# FPGA.net
KiCad netlist of a schematic drawn in Altium Designer
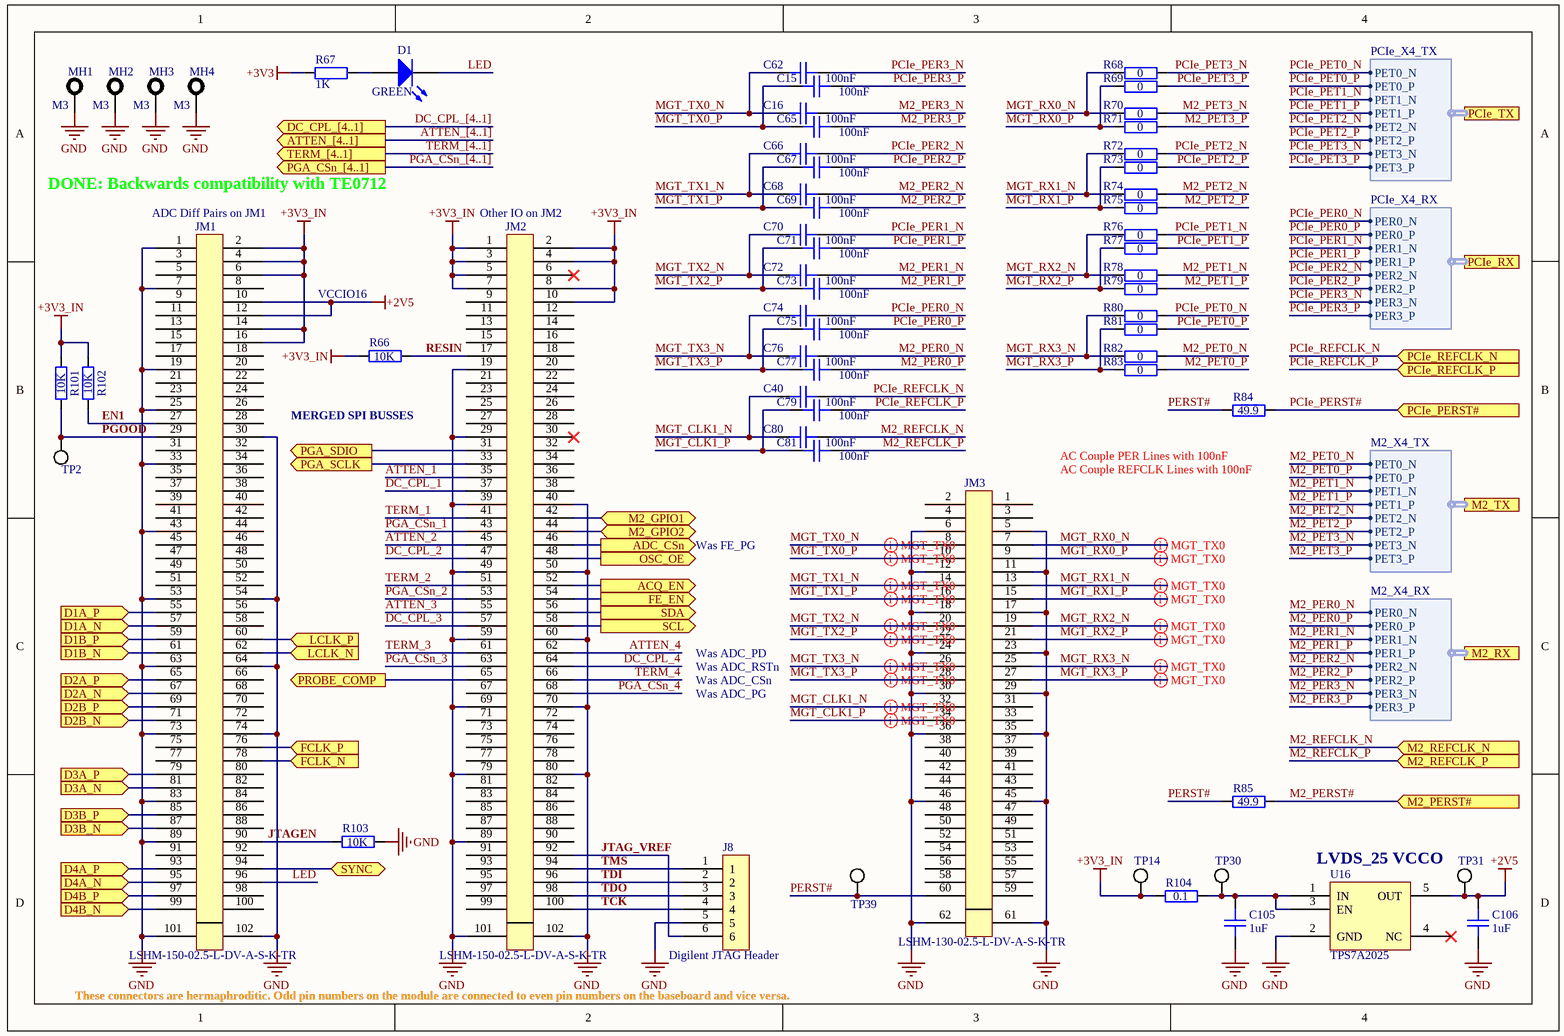
[diagram p0: FPGA.SchDoc]

(export (version "E")
  (design (tool "Eeschema 10.0.6"))
  (components
    (comp (ref "C15")
      (value "100nF")
      (footprint "GEN_C_0201")
      (libsource (lib "DSO") (part "CAP 100nF 6.3V X5R 0201"))
    )
    (comp (ref "C16")
      (value "100nF")
      (footprint "GEN_C_0201")
      (libsource (lib "DSO") (part "CAP 100nF 6.3V X5R 0201"))
    )
    (comp (ref "C40")
      (value "100nF")
      (footprint "GEN_C_0201")
      (libsource (lib "DSO") (part "CAP 100nF 6.3V X5R 0201"))
    )
    (comp (ref "C62")
      (value "100nF")
      (footprint "GEN_C_0201")
      (libsource (lib "DSO") (part "CAP 100nF 6.3V X5R 0201"))
    )
    (comp (ref "C65")
      (value "100nF")
      (footprint "GEN_C_0201")
      (libsource (lib "DSO") (part "CAP 100nF 6.3V X5R 0201"))
    )
    (comp (ref "C66")
      (value "100nF")
      (footprint "GEN_C_0201")
      (libsource (lib "DSO") (part "CAP 100nF 6.3V X5R 0201"))
    )
    (comp (ref "C67")
      (value "100nF")
      (footprint "GEN_C_0201")
      (libsource (lib "DSO") (part "CAP 100nF 6.3V X5R 0201"))
    )
    (comp (ref "C68")
      (value "100nF")
      (footprint "GEN_C_0201")
      (libsource (lib "DSO") (part "CAP 100nF 6.3V X5R 0201"))
    )
    (comp (ref "C69")
      (value "100nF")
      (footprint "GEN_C_0201")
      (libsource (lib "DSO") (part "CAP 100nF 6.3V X5R 0201"))
    )
    (comp (ref "C70")
      (value "100nF")
      (footprint "GEN_C_0201")
      (libsource (lib "DSO") (part "CAP 100nF 6.3V X5R 0201"))
    )
    (comp (ref "C71")
      (value "100nF")
      (footprint "GEN_C_0201")
      (libsource (lib "DSO") (part "CAP 100nF 6.3V X5R 0201"))
    )
    (comp (ref "C72")
      (value "100nF")
      (footprint "GEN_C_0201")
      (libsource (lib "DSO") (part "CAP 100nF 6.3V X5R 0201"))
    )
    (comp (ref "C73")
      (value "100nF")
      (footprint "GEN_C_0201")
      (libsource (lib "DSO") (part "CAP 100nF 6.3V X5R 0201"))
    )
    (comp (ref "C74")
      (value "100nF")
      (footprint "GEN_C_0201")
      (libsource (lib "DSO") (part "CAP 100nF 6.3V X5R 0201"))
    )
    (comp (ref "C75")
      (value "100nF")
      (footprint "GEN_C_0201")
      (libsource (lib "DSO") (part "CAP 100nF 6.3V X5R 0201"))
    )
    (comp (ref "C76")
      (value "100nF")
      (footprint "GEN_C_0201")
      (libsource (lib "DSO") (part "CAP 100nF 6.3V X5R 0201"))
    )
    (comp (ref "C77")
      (value "100nF")
      (footprint "GEN_C_0201")
      (libsource (lib "DSO") (part "CAP 100nF 6.3V X5R 0201"))
    )
    (comp (ref "C79")
      (value "100nF")
      (footprint "GEN_C_0201")
      (libsource (lib "DSO") (part "CAP 100nF 6.3V X5R 0201"))
    )
    (comp (ref "C80")
      (value "100nF")
      (footprint "GEN_C_0201")
      (libsource (lib "DSO") (part "CAP 100nF 6.3V X5R 0201"))
    )
    (comp (ref "C81")
      (value "100nF")
      (footprint "GEN_C_0201")
      (libsource (lib "DSO") (part "CAP 100nF 6.3V X5R 0201"))
    )
    (comp (ref "C105")
      (value "1uF")
      (footprint "GEN_C_0402")
      (libsource (lib "DSO") (part "CAP 1uF 25V X5R 0402"))
    )
    (comp (ref "C106")
      (value "1uF")
      (footprint "GEN_C_0402")
      (libsource (lib "DSO") (part "CAP 1uF 25V X5R 0402"))
    )
    (comp (ref "D1")
      (value "GREEN")
      (footprint "LED_0603_LTST-S270K")
      (libsource (lib "DSO") (part "LED GREEN 0603 LTST-S270K"))
    )
    (comp (ref "J8")
      (value "2.54mm 6 Pin TH")
      (footprint "GEN_2.54mm_6_Pin_TH_RA")
      (libsource (lib "DSO") (part "CONN 2.54mm 6 Pin TH RA"))
    )
    (comp (ref "JM1")
      (value "LSHM-150-02.5-L-DV-A-S-K-TR")
      (footprint "SAM_LSHM-150-XX.X-XX-DV-A-S")
      (fields (field (name "MANUFACTURER") "Samtec"))
      (libsource (lib "DSO") (part "CONN LSHM-150-02.5-L-DV-A-S-K-TR"))
    )
    (comp (ref "JM2")
      (value "LSHM-150-02.5-L-DV-A-S-K-TR")
      (footprint "SAM_LSHM-150-XX.X-XX-DV-A-S")
      (fields (field (name "MANUFACTURER") "Samtec"))
      (libsource (lib "DSO") (part "CONN LSHM-150-02.5-L-DV-A-S-K-TR"))
    )
    (comp (ref "JM3")
      (value "LSHM-130-02.5-L-DV-A-S-K-TR")
      (footprint "SAM_LSHM-130-XX.X-XX-DV-A-S")
      (fields (field (name "MANUFACTURER") "Samtec"))
      (libsource (lib "DSO") (part "CONN LSHM-130-02.5-L-DV-A-S-K-TR"))
    )
    (comp (ref "MH1") (value "M3") (footprint "MH M3") (libsource (lib "DSO") (part "MH M3")))
    (comp (ref "MH2") (value "M3") (footprint "MH M3") (libsource (lib "DSO") (part "MH M3")))
    (comp (ref "MH3") (value "M3") (footprint "MH M3") (libsource (lib "DSO") (part "MH M3")))
    (comp (ref "MH4") (value "M3") (footprint "MH M3") (libsource (lib "DSO") (part "MH M3")))
    (comp (ref "R66")
      (value "10K")
      (footprint "GEN_R_0402")
      (fields (field (name "TOLERANCE") "1%"))
      (libsource (lib "DSO") (part "RES 10K OHM 1% 1/10W 0402"))
    )
    (comp (ref "R67")
      (value "1K")
      (footprint "GEN_R_0402")
      (fields (field (name "TOLERANCE") "1%"))
      (libsource (lib "DSO") (part "RES 1K OHM 1% 1/10W 0402"))
    )
    (comp (ref "R68")
      (value "0")
      (footprint "GEN_R_0201")
      (fields (field (name "TOLERANCE") "1%"))
      (libsource (lib "DSO") (part "RES 0 OHM 1% 1/20W 0201"))
    )
    (comp (ref "R69")
      (value "0")
      (footprint "GEN_R_0201")
      (fields (field (name "TOLERANCE") "1%"))
      (libsource (lib "DSO") (part "RES 0 OHM 1% 1/20W 0201"))
    )
    (comp (ref "R70")
      (value "0")
      (footprint "GEN_R_0201")
      (fields (field (name "TOLERANCE") "1%"))
      (libsource (lib "DSO") (part "RES 0 OHM 1% 1/20W 0201"))
    )
    (comp (ref "R71")
      (value "0")
      (footprint "GEN_R_0201")
      (fields (field (name "TOLERANCE") "1%"))
      (libsource (lib "DSO") (part "RES 0 OHM 1% 1/20W 0201"))
    )
    (comp (ref "R72")
      (value "0")
      (footprint "GEN_R_0201")
      (fields (field (name "TOLERANCE") "1%"))
      (libsource (lib "DSO") (part "RES 0 OHM 1% 1/20W 0201"))
    )
    (comp (ref "R73")
      (value "0")
      (footprint "GEN_R_0201")
      (fields (field (name "TOLERANCE") "1%"))
      (libsource (lib "DSO") (part "RES 0 OHM 1% 1/20W 0201"))
    )
    (comp (ref "R74")
      (value "0")
      (footprint "GEN_R_0201")
      (fields (field (name "TOLERANCE") "1%"))
      (libsource (lib "DSO") (part "RES 0 OHM 1% 1/20W 0201"))
    )
    (comp (ref "R75")
      (value "0")
      (footprint "GEN_R_0201")
      (fields (field (name "TOLERANCE") "1%"))
      (libsource (lib "DSO") (part "RES 0 OHM 1% 1/20W 0201"))
    )
    (comp (ref "R76")
      (value "0")
      (footprint "GEN_R_0201")
      (fields (field (name "TOLERANCE") "1%"))
      (libsource (lib "DSO") (part "RES 0 OHM 1% 1/20W 0201"))
    )
    (comp (ref "R77")
      (value "0")
      (footprint "GEN_R_0201")
      (fields (field (name "TOLERANCE") "1%"))
      (libsource (lib "DSO") (part "RES 0 OHM 1% 1/20W 0201"))
    )
    (comp (ref "R78")
      (value "0")
      (footprint "GEN_R_0201")
      (fields (field (name "TOLERANCE") "1%"))
      (libsource (lib "DSO") (part "RES 0 OHM 1% 1/20W 0201"))
    )
    (comp (ref "R79")
      (value "0")
      (footprint "GEN_R_0201")
      (fields (field (name "TOLERANCE") "1%"))
      (libsource (lib "DSO") (part "RES 0 OHM 1% 1/20W 0201"))
    )
    (comp (ref "R80")
      (value "0")
      (footprint "GEN_R_0201")
      (fields (field (name "TOLERANCE") "1%"))
      (libsource (lib "DSO") (part "RES 0 OHM 1% 1/20W 0201"))
    )
    (comp (ref "R81")
      (value "0")
      (footprint "GEN_R_0201")
      (fields (field (name "TOLERANCE") "1%"))
      (libsource (lib "DSO") (part "RES 0 OHM 1% 1/20W 0201"))
    )
    (comp (ref "R82")
      (value "0")
      (footprint "GEN_R_0201")
      (fields (field (name "TOLERANCE") "1%"))
      (libsource (lib "DSO") (part "RES 0 OHM 1% 1/20W 0201"))
    )
    (comp (ref "R83")
      (value "0")
      (footprint "GEN_R_0201")
      (fields (field (name "TOLERANCE") "1%"))
      (libsource (lib "DSO") (part "RES 0 OHM 1% 1/20W 0201"))
    )
    (comp (ref "R84")
      (value "49.9")
      (footprint "GEN_R_0402")
      (fields (field (name "TOLERANCE") "1%"))
      (libsource (lib "DSO") (part "RES 49.9 OHM 1% 1/10W 0402"))
    )
    (comp (ref "R85")
      (value "49.9")
      (footprint "GEN_R_0402")
      (fields (field (name "TOLERANCE") "1%"))
      (libsource (lib "DSO") (part "RES 49.9 OHM 1% 1/10W 0402"))
    )
    (comp (ref "R101")
      (value "10K")
      (footprint "GEN_R_0402")
      (fields (field (name "TOLERANCE") "1%"))
      (libsource (lib "") (part "RES 10K OHM 1% 1/10W 0402_1"))
    )
    (comp (ref "R102")
      (value "10K")
      (footprint "GEN_R_0402")
      (fields (field (name "TOLERANCE") "1%"))
      (libsource (lib "") (part "RES 10K OHM 1% 1/10W 0402_1"))
    )
    (comp (ref "R103")
      (value "10K")
      (footprint "GEN_R_0402")
      (fields (field (name "TOLERANCE") "1%"))
      (libsource (lib "DSO") (part "RES 10K OHM 1% 1/10W 0402"))
    )
    (comp (ref "R104")
      (value "0.1")
      (footprint "GEN_R_0402")
      (fields (field (name "TOLERANCE") "1%"))
      (libsource (lib "DSO") (part "RES 0.1 OHM 1% 1/6W 0402"))
    )
    (comp (ref "TP2") (value "PCB") (footprint "GEN_TP_PCB") (libsource (lib "DSO") (part "TP PCB 1mm")))
    (comp (ref "TP14") (value "PCB") (footprint "GEN_TP_PCB") (libsource (lib "DSO") (part "TP PCB 1mm")))
    (comp (ref "TP30") (value "PCB") (footprint "GEN_TP_PCB") (libsource (lib "DSO") (part "TP PCB 1mm")))
    (comp (ref "TP31") (value "PCB") (footprint "GEN_TP_PCB") (libsource (lib "DSO") (part "TP PCB 1mm")))
    (comp (ref "TP39") (value "PCB") (footprint "GEN_TP_PCB") (libsource (lib "DSO") (part "TP PCB 1mm")))
    (comp (ref "U16")
      (value "TPS7A2025")
      (footprint "GEN_SOT23_5_950_2900X1600X1450")
      (libsource (lib "DSO") (part "IC LDO TPS7A2025"))
    )
  )
  (nets
    (net (code "5") (name "+2V5") (class "Default")
      (node (ref "C106") (pin "2") (pinfunction "2_2") (pintype "passive"))
      (node (ref "JM1") (pin "10") (pinfunction "10_10") (pintype "passive"))
      (node (ref "JM1") (pin "12") (pinfunction "12_12") (pintype "passive"))
      (node (ref "TP31") (pin "1") (pinfunction "1_1") (pintype "passive"))
      (node (ref "U16") (pin "5") (pinfunction "OUT_5") (pintype "power_in"))
    )
    (net (code "6") (name "+3V3") (class "Default")
      (node (ref "R67") (pin "2") (pinfunction "2_2") (pintype "passive"))
    )
    (net (code "7") (name "+3V3_IN") (class "Default")
      (node (ref "JM1") (pin "14") (pinfunction "14_14") (pintype "passive"))
      (node (ref "JM1") (pin "16") (pinfunction "16_16") (pintype "passive"))
      (node (ref "JM1") (pin "2") (pinfunction "2_2") (pintype "passive"))
      (node (ref "JM1") (pin "4") (pinfunction "4_4") (pintype "passive"))
      (node (ref "JM1") (pin "6") (pinfunction "6_6") (pintype "passive"))
      (node (ref "JM2") (pin "1") (pinfunction "1_1") (pintype "passive"))
      (node (ref "JM2") (pin "10") (pinfunction "10_10") (pintype "passive"))
      (node (ref "JM2") (pin "2") (pinfunction "2_2") (pintype "passive"))
      (node (ref "JM2") (pin "3") (pinfunction "3_3") (pintype "passive"))
      (node (ref "JM2") (pin "4") (pinfunction "4_4") (pintype "passive"))
      (node (ref "JM2") (pin "5") (pinfunction "5_5") (pintype "passive"))
      (node (ref "JM2") (pin "7") (pinfunction "7_7") (pintype "passive"))
      (node (ref "JM2") (pin "8") (pinfunction "8_8") (pintype "passive"))
      (node (ref "R101") (pin "2") (pinfunction "2_2") (pintype "passive"))
      (node (ref "R102") (pin "2") (pinfunction "2_2") (pintype "passive"))
      (node (ref "R104") (pin "1") (pinfunction "1_1") (pintype "passive"))
      (node (ref "R66") (pin "2") (pinfunction "2_2") (pintype "passive"))
      (node (ref "TP14") (pin "1") (pinfunction "1_1") (pintype "passive"))
    )
    (net (code "8") (name "/ACQ_EN") (class "Default")
      (node (ref "JM2") (pin "52") (pinfunction "52_52") (pintype "passive"))
    )
    (net (code "9") (name "/ADC_CSn") (class "Default")
      (node (ref "JM2") (pin "46") (pinfunction "46_46") (pintype "passive"))
    )
    (net (code "10") (name "/ATTEN_1") (class "Default")
      (node (ref "JM2") (pin "35") (pinfunction "35_35") (pintype "passive"))
    )
    (net (code "11") (name "/ATTEN_2") (class "Default")
      (node (ref "JM2") (pin "45") (pinfunction "45_45") (pintype "passive"))
    )
    (net (code "12") (name "/ATTEN_3") (class "Default")
      (node (ref "JM2") (pin "55") (pinfunction "55_55") (pintype "passive"))
    )
    (net (code "13") (name "/ATTEN_4") (class "Default")
      (node (ref "JM2") (pin "62") (pinfunction "62_62") (pintype "passive"))
    )
    (net (code "15") (name "/D1A_N") (class "Default")
      (node (ref "JM1") (pin "57") (pinfunction "57_57") (pintype "passive"))
    )
    (net (code "16") (name "/D1A_P") (class "Default")
      (node (ref "JM1") (pin "55") (pinfunction "55_55") (pintype "passive"))
    )
    (net (code "17") (name "/D1B_N") (class "Default")
      (node (ref "JM1") (pin "61") (pinfunction "61_61") (pintype "passive"))
    )
    (net (code "18") (name "/D1B_P") (class "Default")
      (node (ref "JM1") (pin "59") (pinfunction "59_59") (pintype "passive"))
    )
    (net (code "19") (name "/D2A_N") (class "Default")
      (node (ref "JM1") (pin "67") (pinfunction "67_67") (pintype "passive"))
    )
    (net (code "20") (name "/D2A_P") (class "Default")
      (node (ref "JM1") (pin "65") (pinfunction "65_65") (pintype "passive"))
    )
    (net (code "21") (name "/D2B_N") (class "Default")
      (node (ref "JM1") (pin "71") (pinfunction "71_71") (pintype "passive"))
    )
    (net (code "22") (name "/D2B_P") (class "Default")
      (node (ref "JM1") (pin "69") (pinfunction "69_69") (pintype "passive"))
    )
    (net (code "23") (name "/D3A_N") (class "Default")
      (node (ref "JM1") (pin "81") (pinfunction "81_81") (pintype "passive"))
    )
    (net (code "24") (name "/D3A_P") (class "Default")
      (node (ref "JM1") (pin "79") (pinfunction "79_79") (pintype "passive"))
    )
    (net (code "25") (name "/D3B_N") (class "Default")
      (node (ref "JM1") (pin "87") (pinfunction "87_87") (pintype "passive"))
    )
    (net (code "26") (name "/D3B_P") (class "Default")
      (node (ref "JM1") (pin "85") (pinfunction "85_85") (pintype "passive"))
    )
    (net (code "27") (name "/D4A_N") (class "Default")
      (node (ref "JM1") (pin "95") (pinfunction "95_95") (pintype "passive"))
    )
    (net (code "28") (name "/D4A_P") (class "Default")
      (node (ref "JM1") (pin "93") (pinfunction "93_93") (pintype "passive"))
    )
    (net (code "29") (name "/D4B_N") (class "Default")
      (node (ref "JM1") (pin "99") (pinfunction "99_99") (pintype "passive"))
    )
    (net (code "30") (name "/D4B_P") (class "Default")
      (node (ref "JM1") (pin "97") (pinfunction "97_97") (pintype "passive"))
    )
    (net (code "31") (name "/DC_CPL_1") (class "Default")
      (node (ref "JM2") (pin "37") (pinfunction "37_37") (pintype "passive"))
    )
    (net (code "32") (name "/DC_CPL_2") (class "Default")
      (node (ref "JM2") (pin "47") (pinfunction "47_47") (pintype "passive"))
    )
    (net (code "33") (name "/DC_CPL_3") (class "Default")
      (node (ref "JM2") (pin "57") (pinfunction "57_57") (pintype "passive"))
    )
    (net (code "34") (name "/DC_CPL_4") (class "Default")
      (node (ref "JM2") (pin "64") (pinfunction "64_64") (pintype "passive"))
    )
    (net (code "36") (name "/EN1") (class "Default")
      (node (ref "JM1") (pin "27") (pinfunction "27_27") (pintype "passive"))
      (node (ref "R102") (pin "1") (pinfunction "1_1") (pintype "passive"))
    )
    (net (code "37") (name "/FCLK_N") (class "Default")
      (node (ref "JM1") (pin "78") (pinfunction "78_78") (pintype "passive"))
    )
    (net (code "38") (name "/FCLK_P") (class "Default")
      (node (ref "JM1") (pin "76") (pinfunction "76_76") (pintype "passive"))
    )
    (net (code "39") (name "/FE_EN") (class "Default")
      (node (ref "JM2") (pin "54") (pinfunction "54_54") (pintype "passive"))
    )
    (net (code "40") (name "/JTAGEN") (class "Default")
      (node (ref "JM1") (pin "90") (pinfunction "90_90") (pintype "passive"))
      (node (ref "R103") (pin "2") (pinfunction "2_2") (pintype "passive"))
    )
    (net (code "41") (name "/JTAG_VREF") (class "Default")
      (node (ref "J8") (pin "6") (pinfunction "6_6") (pintype "passive"))
      (node (ref "JM2") (pin "92") (pinfunction "92_92") (pintype "passive"))
    )
    (net (code "42") (name "/LCLK_N") (class "Default")
      (node (ref "JM1") (pin "62") (pinfunction "62_62") (pintype "passive"))
    )
    (net (code "43") (name "/LCLK_P") (class "Default")
      (node (ref "JM1") (pin "60") (pinfunction "60_60") (pintype "passive"))
    )
    (net (code "44") (name "/LED") (class "Default")
      (node (ref "D1") (pin "1") (pinfunction "K_1") (pintype "passive"))
      (node (ref "JM1") (pin "96") (pinfunction "96_96") (pintype "passive"))
    )
    (net (code "45") (name "/M2_GPIO1") (class "Default")
      (node (ref "JM2") (pin "42") (pinfunction "42_42") (pintype "passive"))
    )
    (net (code "46") (name "/M2_GPIO2") (class "Default")
      (node (ref "JM2") (pin "44") (pinfunction "44_44") (pintype "passive"))
    )
    (net (code "47") (name "/M2_PER0_N") (class "Default")
      (node (ref "C76") (pin "1") (pinfunction "1_1") (pintype "passive"))
    )
    (net (code "48") (name "/M2_PER0_P") (class "Default")
      (node (ref "C77") (pin "1") (pinfunction "1_1") (pintype "passive"))
    )
    (net (code "49") (name "/M2_PER1_N") (class "Default")
      (node (ref "C72") (pin "1") (pinfunction "1_1") (pintype "passive"))
    )
    (net (code "50") (name "/M2_PER1_P") (class "Default")
      (node (ref "C73") (pin "1") (pinfunction "1_1") (pintype "passive"))
    )
    (net (code "51") (name "/M2_PER2_N") (class "Default")
      (node (ref "C68") (pin "1") (pinfunction "1_1") (pintype "passive"))
    )
    (net (code "52") (name "/M2_PER2_P") (class "Default")
      (node (ref "C69") (pin "1") (pinfunction "1_1") (pintype "passive"))
    )
    (net (code "53") (name "/M2_PER3_N") (class "Default")
      (node (ref "C16") (pin "1") (pinfunction "1_1") (pintype "passive"))
    )
    (net (code "54") (name "/M2_PER3_P") (class "Default")
      (node (ref "C65") (pin "1") (pinfunction "1_1") (pintype "passive"))
    )
    (net (code "55") (name "/M2_PERST#") (class "Default")
      (node (ref "R85") (pin "2") (pinfunction "2_2") (pintype "passive"))
    )
    (net (code "56") (name "/M2_PET0_N") (class "Default")
      (node (ref "R82") (pin "2") (pinfunction "2_2") (pintype "passive"))
    )
    (net (code "57") (name "/M2_PET0_P") (class "Default")
      (node (ref "R83") (pin "2") (pinfunction "2_2") (pintype "passive"))
    )
    (net (code "58") (name "/M2_PET1_N") (class "Default")
      (node (ref "R78") (pin "2") (pinfunction "2_2") (pintype "passive"))
    )
    (net (code "59") (name "/M2_PET1_P") (class "Default")
      (node (ref "R79") (pin "2") (pinfunction "2_2") (pintype "passive"))
    )
    (net (code "60") (name "/M2_PET2_N") (class "Default")
      (node (ref "R74") (pin "2") (pinfunction "2_2") (pintype "passive"))
    )
    (net (code "61") (name "/M2_PET2_P") (class "Default")
      (node (ref "R75") (pin "2") (pinfunction "2_2") (pintype "passive"))
    )
    (net (code "62") (name "/M2_PET3_N") (class "Default")
      (node (ref "R70") (pin "2") (pinfunction "2_2") (pintype "passive"))
    )
    (net (code "63") (name "/M2_PET3_P") (class "Default")
      (node (ref "R71") (pin "2") (pinfunction "2_2") (pintype "passive"))
    )
    (net (code "64") (name "/M2_REFCLK_N") (class "Default")
      (node (ref "C80") (pin "1") (pinfunction "1_1") (pintype "passive"))
    )
    (net (code "65") (name "/M2_REFCLK_P") (class "Default")
      (node (ref "C81") (pin "1") (pinfunction "1_1") (pintype "passive"))
    )
    (net (code "66") (name "/MGT_CLK1_N") (class "Default")
      (node (ref "C40") (pin "2") (pinfunction "2_2") (pintype "passive"))
      (node (ref "C80") (pin "2") (pinfunction "2_2") (pintype "passive"))
      (node (ref "JM3") (pin "32") (pinfunction "32_32") (pintype "passive"))
    )
    (net (code "67") (name "/MGT_CLK1_P") (class "Default")
      (node (ref "C79") (pin "2") (pinfunction "2_2") (pintype "passive"))
      (node (ref "C81") (pin "2") (pinfunction "2_2") (pintype "passive"))
      (node (ref "JM3") (pin "34") (pinfunction "34_34") (pintype "passive"))
    )
    (net (code "68") (name "/MGT_RX0_N") (class "Default")
      (node (ref "JM3") (pin "7") (pinfunction "7_7") (pintype "passive"))
      (node (ref "R68") (pin "1") (pinfunction "1_1") (pintype "passive"))
      (node (ref "R70") (pin "1") (pinfunction "1_1") (pintype "passive"))
    )
    (net (code "69") (name "/MGT_RX0_P") (class "Default")
      (node (ref "JM3") (pin "9") (pinfunction "9_9") (pintype "passive"))
      (node (ref "R69") (pin "1") (pinfunction "1_1") (pintype "passive"))
      (node (ref "R71") (pin "1") (pinfunction "1_1") (pintype "passive"))
    )
    (net (code "70") (name "/MGT_RX1_N") (class "Default")
      (node (ref "JM3") (pin "13") (pinfunction "13_13") (pintype "passive"))
      (node (ref "R72") (pin "1") (pinfunction "1_1") (pintype "passive"))
      (node (ref "R74") (pin "1") (pinfunction "1_1") (pintype "passive"))
    )
    (net (code "71") (name "/MGT_RX1_P") (class "Default")
      (node (ref "JM3") (pin "15") (pinfunction "15_15") (pintype "passive"))
      (node (ref "R73") (pin "1") (pinfunction "1_1") (pintype "passive"))
      (node (ref "R75") (pin "1") (pinfunction "1_1") (pintype "passive"))
    )
    (net (code "72") (name "/MGT_RX2_N") (class "Default")
      (node (ref "JM3") (pin "19") (pinfunction "19_19") (pintype "passive"))
      (node (ref "R76") (pin "1") (pinfunction "1_1") (pintype "passive"))
      (node (ref "R78") (pin "1") (pinfunction "1_1") (pintype "passive"))
    )
    (net (code "73") (name "/MGT_RX2_P") (class "Default")
      (node (ref "JM3") (pin "21") (pinfunction "21_21") (pintype "passive"))
      (node (ref "R77") (pin "1") (pinfunction "1_1") (pintype "passive"))
      (node (ref "R79") (pin "1") (pinfunction "1_1") (pintype "passive"))
    )
    (net (code "74") (name "/MGT_RX3_N") (class "Default")
      (node (ref "JM3") (pin "25") (pinfunction "25_25") (pintype "passive"))
      (node (ref "R80") (pin "1") (pinfunction "1_1") (pintype "passive"))
      (node (ref "R82") (pin "1") (pinfunction "1_1") (pintype "passive"))
    )
    (net (code "75") (name "/MGT_RX3_P") (class "Default")
      (node (ref "JM3") (pin "27") (pinfunction "27_27") (pintype "passive"))
      (node (ref "R81") (pin "1") (pinfunction "1_1") (pintype "passive"))
      (node (ref "R83") (pin "1") (pinfunction "1_1") (pintype "passive"))
    )
    (net (code "76") (name "/MGT_TX0_N") (class "Default")
      (node (ref "C16") (pin "2") (pinfunction "2_2") (pintype "passive"))
      (node (ref "C62") (pin "2") (pinfunction "2_2") (pintype "passive"))
      (node (ref "JM3") (pin "8") (pinfunction "8_8") (pintype "passive"))
    )
    (net (code "77") (name "/MGT_TX0_P") (class "Default")
      (node (ref "C15") (pin "2") (pinfunction "2_2") (pintype "passive"))
      (node (ref "C65") (pin "2") (pinfunction "2_2") (pintype "passive"))
      (node (ref "JM3") (pin "10") (pinfunction "10_10") (pintype "passive"))
    )
    (net (code "78") (name "/MGT_TX1_N") (class "Default")
      (node (ref "C66") (pin "2") (pinfunction "2_2") (pintype "passive"))
      (node (ref "C68") (pin "2") (pinfunction "2_2") (pintype "passive"))
      (node (ref "JM3") (pin "14") (pinfunction "14_14") (pintype "passive"))
    )
    (net (code "79") (name "/MGT_TX1_P") (class "Default")
      (node (ref "C67") (pin "2") (pinfunction "2_2") (pintype "passive"))
      (node (ref "C69") (pin "2") (pinfunction "2_2") (pintype "passive"))
      (node (ref "JM3") (pin "16") (pinfunction "16_16") (pintype "passive"))
    )
    (net (code "80") (name "/MGT_TX2_N") (class "Default")
      (node (ref "C70") (pin "2") (pinfunction "2_2") (pintype "passive"))
      (node (ref "C72") (pin "2") (pinfunction "2_2") (pintype "passive"))
      (node (ref "JM3") (pin "20") (pinfunction "20_20") (pintype "passive"))
    )
    (net (code "81") (name "/MGT_TX2_P") (class "Default")
      (node (ref "C71") (pin "2") (pinfunction "2_2") (pintype "passive"))
      (node (ref "C73") (pin "2") (pinfunction "2_2") (pintype "passive"))
      (node (ref "JM3") (pin "22") (pinfunction "22_22") (pintype "passive"))
    )
    (net (code "82") (name "/MGT_TX3_N") (class "Default")
      (node (ref "C74") (pin "2") (pinfunction "2_2") (pintype "passive"))
      (node (ref "C76") (pin "2") (pinfunction "2_2") (pintype "passive"))
      (node (ref "JM3") (pin "26") (pinfunction "26_26") (pintype "passive"))
    )
    (net (code "83") (name "/MGT_TX3_P") (class "Default")
      (node (ref "C75") (pin "2") (pinfunction "2_2") (pintype "passive"))
      (node (ref "C77") (pin "2") (pinfunction "2_2") (pintype "passive"))
      (node (ref "JM3") (pin "28") (pinfunction "28_28") (pintype "passive"))
    )
    (net (code "84") (name "/OSC_OE") (class "Default")
      (node (ref "JM2") (pin "48") (pinfunction "48_48") (pintype "passive"))
    )
    (net (code "85") (name "/PCIe_PER0_N") (class "Default")
      (node (ref "C74") (pin "1") (pinfunction "1_1") (pintype "passive"))
    )
    (net (code "86") (name "/PCIe_PER0_P") (class "Default")
      (node (ref "C75") (pin "1") (pinfunction "1_1") (pintype "passive"))
    )
    (net (code "87") (name "/PCIe_PER1_N") (class "Default")
      (node (ref "C70") (pin "1") (pinfunction "1_1") (pintype "passive"))
    )
    (net (code "88") (name "/PCIe_PER1_P") (class "Default")
      (node (ref "C71") (pin "1") (pinfunction "1_1") (pintype "passive"))
    )
    (net (code "89") (name "/PCIe_PER2_N") (class "Default")
      (node (ref "C66") (pin "1") (pinfunction "1_1") (pintype "passive"))
    )
    (net (code "90") (name "/PCIe_PER2_P") (class "Default")
      (node (ref "C67") (pin "1") (pinfunction "1_1") (pintype "passive"))
    )
    (net (code "91") (name "/PCIe_PER3_N") (class "Default")
      (node (ref "C62") (pin "1") (pinfunction "1_1") (pintype "passive"))
    )
    (net (code "92") (name "/PCIe_PER3_P") (class "Default")
      (node (ref "C15") (pin "1") (pinfunction "1_1") (pintype "passive"))
    )
    (net (code "93") (name "/PCIe_PERST#") (class "Default")
      (node (ref "R84") (pin "2") (pinfunction "2_2") (pintype "passive"))
    )
    (net (code "94") (name "/PCIe_PET0_N") (class "Default")
      (node (ref "R80") (pin "2") (pinfunction "2_2") (pintype "passive"))
    )
    (net (code "95") (name "/PCIe_PET0_P") (class "Default")
      (node (ref "R81") (pin "2") (pinfunction "2_2") (pintype "passive"))
    )
    (net (code "96") (name "/PCIe_PET1_N") (class "Default")
      (node (ref "R76") (pin "2") (pinfunction "2_2") (pintype "passive"))
    )
    (net (code "97") (name "/PCIe_PET1_P") (class "Default")
      (node (ref "R77") (pin "2") (pinfunction "2_2") (pintype "passive"))
    )
    (net (code "98") (name "/PCIe_PET2_N") (class "Default")
      (node (ref "R72") (pin "2") (pinfunction "2_2") (pintype "passive"))
    )
    (net (code "99") (name "/PCIe_PET2_P") (class "Default")
      (node (ref "R73") (pin "2") (pinfunction "2_2") (pintype "passive"))
    )
    (net (code "100") (name "/PCIe_PET3_N") (class "Default")
      (node (ref "R68") (pin "2") (pinfunction "2_2") (pintype "passive"))
    )
    (net (code "101") (name "/PCIe_PET3_P") (class "Default")
      (node (ref "R69") (pin "2") (pinfunction "2_2") (pintype "passive"))
    )
    (net (code "102") (name "/PCIe_REFCLK_N") (class "Default")
      (node (ref "C40") (pin "1") (pinfunction "1_1") (pintype "passive"))
    )
    (net (code "103") (name "/PCIe_REFCLK_P") (class "Default")
      (node (ref "C79") (pin "1") (pinfunction "1_1") (pintype "passive"))
    )
    (net (code "104") (name "/PERST#") (class "Default")
      (node (ref "JM3") (pin "60") (pinfunction "60_60") (pintype "passive"))
      (node (ref "R84") (pin "1") (pinfunction "1_1") (pintype "passive"))
      (node (ref "R85") (pin "1") (pinfunction "1_1") (pintype "passive"))
      (node (ref "TP39") (pin "1") (pinfunction "1_1") (pintype "passive"))
    )
    (net (code "105") (name "/PGA_CSn_1") (class "Default")
      (node (ref "JM2") (pin "43") (pinfunction "43_43") (pintype "passive"))
    )
    (net (code "106") (name "/PGA_CSn_2") (class "Default")
      (node (ref "JM2") (pin "53") (pinfunction "53_53") (pintype "passive"))
    )
    (net (code "107") (name "/PGA_CSn_3") (class "Default")
      (node (ref "JM2") (pin "63") (pinfunction "63_63") (pintype "passive"))
    )
    (net (code "108") (name "/PGA_CSn_4") (class "Default")
      (node (ref "JM2") (pin "68") (pinfunction "68_68") (pintype "passive"))
    )
    (net (code "110") (name "/PGA_SCLK") (class "Default")
      (node (ref "JM2") (pin "33") (pinfunction "33_33") (pintype "passive"))
    )
    (net (code "111") (name "/PGA_SDIO") (class "Default")
      (node (ref "JM2") (pin "31") (pinfunction "31_31") (pintype "passive"))
    )
    (net (code "112") (name "/PGOOD") (class "Default")
      (node (ref "JM1") (pin "29") (pinfunction "29_29") (pintype "passive"))
      (node (ref "R101") (pin "1") (pinfunction "1_1") (pintype "passive"))
      (node (ref "TP2") (pin "1") (pinfunction "1_1") (pintype "passive"))
    )
    (net (code "113") (name "/PROBE_COMP") (class "Default")
      (node (ref "JM2") (pin "65") (pinfunction "65_65") (pintype "passive"))
    )
    (net (code "114") (name "/RESIN") (class "Default")
      (node (ref "JM2") (pin "17") (pinfunction "17_17") (pintype "passive"))
      (node (ref "R66") (pin "1") (pinfunction "1_1") (pintype "passive"))
    )
    (net (code "115") (name "/SCL") (class "Default")
      (node (ref "JM2") (pin "58") (pinfunction "58_58") (pintype "passive"))
    )
    (net (code "116") (name "/SDA") (class "Default")
      (node (ref "JM2") (pin "56") (pinfunction "56_56") (pintype "passive"))
    )
    (net (code "117") (name "/SYNC") (class "Default")
      (node (ref "JM1") (pin "94") (pinfunction "94_94") (pintype "passive"))
    )
    (net (code "118") (name "/TCK") (class "Default")
      (node (ref "J8") (pin "4") (pinfunction "4_4") (pintype "passive"))
      (node (ref "JM2") (pin "100") (pinfunction "100_100") (pintype "passive"))
    )
    (net (code "119") (name "/TDI") (class "Default")
      (node (ref "J8") (pin "2") (pinfunction "2_2") (pintype "passive"))
      (node (ref "JM2") (pin "96") (pinfunction "96_96") (pintype "passive"))
    )
    (net (code "120") (name "/TDO") (class "Default")
      (node (ref "J8") (pin "3") (pinfunction "3_3") (pintype "passive"))
      (node (ref "JM2") (pin "98") (pinfunction "98_98") (pintype "passive"))
    )
    (net (code "121") (name "/TERM_1") (class "Default")
      (node (ref "JM2") (pin "41") (pinfunction "41_41") (pintype "passive"))
    )
    (net (code "122") (name "/TERM_2") (class "Default")
      (node (ref "JM2") (pin "51") (pinfunction "51_51") (pintype "passive"))
    )
    (net (code "123") (name "/TERM_3") (class "Default")
      (node (ref "JM2") (pin "61") (pinfunction "61_61") (pintype "passive"))
    )
    (net (code "124") (name "/TERM_4") (class "Default")
      (node (ref "JM2") (pin "66") (pinfunction "66_66") (pintype "passive"))
    )
    (net (code "126") (name "/TMS") (class "Default")
      (node (ref "J8") (pin "1") (pinfunction "1_1") (pintype "passive"))
      (node (ref "JM2") (pin "94") (pinfunction "94_94") (pintype "passive"))
    )
    (net (code "131") (name "GND") (class "Default")
      (node (ref "C105") (pin "1") (pinfunction "1_1") (pintype "passive"))
      (node (ref "C106") (pin "1") (pinfunction "1_1") (pintype "passive"))
      (node (ref "J8") (pin "5") (pinfunction "5_5") (pintype "passive"))
      (node (ref "JM1") (pin "1") (pinfunction "1_1") (pintype "passive"))
      (node (ref "JM1") (pin "101") (pinfunction "101_101") (pintype "passive"))
      (node (ref "JM1") (pin "102") (pinfunction "102_102") (pintype "passive"))
      (node (ref "JM1") (pin "19") (pinfunction "19_19") (pintype "passive"))
      (node (ref "JM1") (pin "25") (pinfunction "25_25") (pintype "passive"))
      (node (ref "JM1") (pin "30") (pinfunction "30_30") (pintype "passive"))
      (node (ref "JM1") (pin "33") (pinfunction "33_33") (pintype "passive"))
      (node (ref "JM1") (pin "43") (pinfunction "43_43") (pintype "passive"))
      (node (ref "JM1") (pin "53") (pinfunction "53_53") (pintype "passive"))
      (node (ref "JM1") (pin "54") (pinfunction "54_54") (pintype "passive"))
      (node (ref "JM1") (pin "63") (pinfunction "63_63") (pintype "passive"))
      (node (ref "JM1") (pin "64") (pinfunction "64_64") (pintype "passive"))
      (node (ref "JM1") (pin "7") (pinfunction "7_7") (pintype "passive"))
      (node (ref "JM1") (pin "73") (pinfunction "73_73") (pintype "passive"))
      (node (ref "JM1") (pin "74") (pinfunction "74_74") (pintype "passive"))
      (node (ref "JM1") (pin "83") (pinfunction "83_83") (pintype "passive"))
      (node (ref "JM1") (pin "89") (pinfunction "89_89") (pintype "passive"))
      (node (ref "JM2") (pin "101") (pinfunction "101_101") (pintype "passive"))
      (node (ref "JM2") (pin "102") (pinfunction "102_102") (pintype "passive"))
      (node (ref "JM2") (pin "19") (pinfunction "19_19") (pintype "passive"))
      (node (ref "JM2") (pin "29") (pinfunction "29_29") (pintype "passive"))
      (node (ref "JM2") (pin "39") (pinfunction "39_39") (pintype "passive"))
      (node (ref "JM2") (pin "40") (pinfunction "40_40") (pintype "passive"))
      (node (ref "JM2") (pin "49") (pinfunction "49_49") (pintype "passive"))
      (node (ref "JM2") (pin "50") (pinfunction "50_50") (pintype "passive"))
      (node (ref "JM2") (pin "59") (pinfunction "59_59") (pintype "passive"))
      (node (ref "JM2") (pin "60") (pinfunction "60_60") (pintype "passive"))
      (node (ref "JM2") (pin "69") (pinfunction "69_69") (pintype "passive"))
      (node (ref "JM2") (pin "70") (pinfunction "70_70") (pintype "passive"))
      (node (ref "JM2") (pin "79") (pinfunction "79_79") (pintype "passive"))
      (node (ref "JM2") (pin "80") (pinfunction "80_80") (pintype "passive"))
      (node (ref "JM2") (pin "89") (pinfunction "89_89") (pintype "passive"))
      (node (ref "JM3") (pin "11") (pinfunction "11_11") (pintype "passive"))
      (node (ref "JM3") (pin "12") (pinfunction "12_12") (pintype "passive"))
      (node (ref "JM3") (pin "17") (pinfunction "17_17") (pintype "passive"))
      (node (ref "JM3") (pin "18") (pinfunction "18_18") (pintype "passive"))
      (node (ref "JM3") (pin "23") (pinfunction "23_23") (pintype "passive"))
      (node (ref "JM3") (pin "24") (pinfunction "24_24") (pintype "passive"))
      (node (ref "JM3") (pin "29") (pinfunction "29_29") (pintype "passive"))
      (node (ref "JM3") (pin "30") (pinfunction "30_30") (pintype "passive"))
      (node (ref "JM3") (pin "35") (pinfunction "35_35") (pintype "passive"))
      (node (ref "JM3") (pin "36") (pinfunction "36_36") (pintype "passive"))
      (node (ref "JM3") (pin "45") (pinfunction "45_45") (pintype "passive"))
      (node (ref "JM3") (pin "46") (pinfunction "46_46") (pintype "passive"))
      (node (ref "JM3") (pin "5") (pinfunction "5_5") (pintype "passive"))
      (node (ref "JM3") (pin "6") (pinfunction "6_6") (pintype "passive"))
      (node (ref "JM3") (pin "61") (pinfunction "61_61") (pintype "passive"))
      (node (ref "JM3") (pin "62") (pinfunction "62_62") (pintype "passive"))
      (node (ref "MH1") (pin "1") (pinfunction "1_1") (pintype "passive"))
      (node (ref "MH2") (pin "1") (pinfunction "1_1") (pintype "passive"))
      (node (ref "MH3") (pin "1") (pinfunction "1_1") (pintype "passive"))
      (node (ref "MH4") (pin "1") (pinfunction "1_1") (pintype "passive"))
      (node (ref "R103") (pin "1") (pinfunction "1_1") (pintype "passive"))
      (node (ref "U16") (pin "2") (pinfunction "GND_2") (pintype "power_in"))
    )
    (net (code "132") (name "Net-(D1-A)") (class "Default")
      (node (ref "D1") (pin "2") (pinfunction "A_2") (pintype "passive"))
      (node (ref "R67") (pin "1") (pinfunction "1_1") (pintype "passive"))
    )
    (net (code "133") (name "Net-(U16-EN)") (class "Default")
      (node (ref "C105") (pin "2") (pinfunction "2_2") (pintype "passive"))
      (node (ref "R104") (pin "2") (pinfunction "2_2") (pintype "passive"))
      (node (ref "TP30") (pin "1") (pinfunction "1_1") (pintype "passive"))
      (node (ref "U16") (pin "1") (pinfunction "IN_1") (pintype "power_in"))
      (node (ref "U16") (pin "3") (pinfunction "EN_3") (pintype "passive"))
    )
    (net (code "134") (name "unconnected-(JM1-Pad3)") (class "Default")
      (node (ref "JM1") (pin "3") (pinfunction "3_3") (pintype "passive"))
    )
    (net (code "135") (name "unconnected-(JM1-Pad5)") (class "Default")
      (node (ref "JM1") (pin "5") (pinfunction "5_5") (pintype "passive"))
    )
    (net (code "136") (name "unconnected-(JM1-Pad8)") (class "Default")
      (node (ref "JM1") (pin "8") (pinfunction "8_8") (pintype "passive"))
    )
    (net (code "137") (name "unconnected-(JM1-Pad9)") (class "Default")
      (node (ref "JM1") (pin "9") (pinfunction "9_9") (pintype "passive"))
    )
    (net (code "138") (name "unconnected-(JM1-Pad11)") (class "Default")
      (node (ref "JM1") (pin "11") (pinfunction "11_11") (pintype "passive"))
    )
    (net (code "139") (name "unconnected-(JM1-Pad13)") (class "Default")
      (node (ref "JM1") (pin "13") (pinfunction "13_13") (pintype "passive"))
    )
    (net (code "140") (name "unconnected-(JM1-Pad15)") (class "Default")
      (node (ref "JM1") (pin "15") (pinfunction "15_15") (pintype "passive"))
    )
    (net (code "141") (name "unconnected-(JM1-Pad17)") (class "Default")
      (node (ref "JM1") (pin "17") (pinfunction "17_17") (pintype "passive"))
    )
    (net (code "142") (name "unconnected-(JM1-Pad18)") (class "Default")
      (node (ref "JM1") (pin "18") (pinfunction "18_18") (pintype "passive"))
    )
    (net (code "143") (name "unconnected-(JM1-Pad20)") (class "Default")
      (node (ref "JM1") (pin "20") (pinfunction "20_20") (pintype "passive"))
    )
    (net (code "144") (name "unconnected-(JM1-Pad21)") (class "Default")
      (node (ref "JM1") (pin "21") (pinfunction "21_21") (pintype "passive"))
    )
    (net (code "145") (name "unconnected-(JM1-Pad22)") (class "Default")
      (node (ref "JM1") (pin "22") (pinfunction "22_22") (pintype "passive"))
    )
    (net (code "146") (name "unconnected-(JM1-Pad23)") (class "Default")
      (node (ref "JM1") (pin "23") (pinfunction "23_23") (pintype "passive"))
    )
    (net (code "147") (name "unconnected-(JM1-Pad24)") (class "Default")
      (node (ref "JM1") (pin "24") (pinfunction "24_24") (pintype "passive"))
    )
    (net (code "148") (name "unconnected-(JM1-Pad26)") (class "Default")
      (node (ref "JM1") (pin "26") (pinfunction "26_26") (pintype "passive"))
    )
    (net (code "149") (name "unconnected-(JM1-Pad28)") (class "Default")
      (node (ref "JM1") (pin "28") (pinfunction "28_28") (pintype "passive"))
    )
    (net (code "150") (name "unconnected-(JM1-Pad31)") (class "Default")
      (node (ref "JM1") (pin "31") (pinfunction "31_31") (pintype "passive"))
    )
    (net (code "151") (name "unconnected-(JM1-Pad32)") (class "Default")
      (node (ref "JM1") (pin "32") (pinfunction "32_32") (pintype "passive"))
    )
    (net (code "152") (name "unconnected-(JM1-Pad34)") (class "Default")
      (node (ref "JM1") (pin "34") (pinfunction "34_34") (pintype "passive"))
    )
    (net (code "153") (name "unconnected-(JM1-Pad35)") (class "Default")
      (node (ref "JM1") (pin "35") (pinfunction "35_35") (pintype "passive"))
    )
    (net (code "154") (name "unconnected-(JM1-Pad36)") (class "Default")
      (node (ref "JM1") (pin "36") (pinfunction "36_36") (pintype "passive"))
    )
    (net (code "155") (name "unconnected-(JM1-Pad37)") (class "Default")
      (node (ref "JM1") (pin "37") (pinfunction "37_37") (pintype "passive"))
    )
    (net (code "156") (name "unconnected-(JM1-Pad38)") (class "Default")
      (node (ref "JM1") (pin "38") (pinfunction "38_38") (pintype "passive"))
    )
    (net (code "157") (name "unconnected-(JM1-Pad39)") (class "Default")
      (node (ref "JM1") (pin "39") (pinfunction "39_39") (pintype "passive"))
    )
    (net (code "158") (name "unconnected-(JM1-Pad40)") (class "Default")
      (node (ref "JM1") (pin "40") (pinfunction "40_40") (pintype "passive"))
    )
    (net (code "159") (name "unconnected-(JM1-Pad41)") (class "Default")
      (node (ref "JM1") (pin "41") (pinfunction "41_41") (pintype "passive"))
    )
    (net (code "160") (name "unconnected-(JM1-Pad42)") (class "Default")
      (node (ref "JM1") (pin "42") (pinfunction "42_42") (pintype "passive"))
    )
    (net (code "161") (name "unconnected-(JM1-Pad44)") (class "Default")
      (node (ref "JM1") (pin "44") (pinfunction "44_44") (pintype "passive"))
    )
    (net (code "162") (name "unconnected-(JM1-Pad45)") (class "Default")
      (node (ref "JM1") (pin "45") (pinfunction "45_45") (pintype "passive"))
    )
    (net (code "163") (name "unconnected-(JM1-Pad46)") (class "Default")
      (node (ref "JM1") (pin "46") (pinfunction "46_46") (pintype "passive"))
    )
    (net (code "164") (name "unconnected-(JM1-Pad47)") (class "Default")
      (node (ref "JM1") (pin "47") (pinfunction "47_47") (pintype "passive"))
    )
    (net (code "165") (name "unconnected-(JM1-Pad48)") (class "Default")
      (node (ref "JM1") (pin "48") (pinfunction "48_48") (pintype "passive"))
    )
    (net (code "166") (name "unconnected-(JM1-Pad49)") (class "Default")
      (node (ref "JM1") (pin "49") (pinfunction "49_49") (pintype "passive"))
    )
    (net (code "167") (name "unconnected-(JM1-Pad50)") (class "Default")
      (node (ref "JM1") (pin "50") (pinfunction "50_50") (pintype "passive"))
    )
    (net (code "168") (name "unconnected-(JM1-Pad51)") (class "Default")
      (node (ref "JM1") (pin "51") (pinfunction "51_51") (pintype "passive"))
    )
    (net (code "169") (name "unconnected-(JM1-Pad52)") (class "Default")
      (node (ref "JM1") (pin "52") (pinfunction "52_52") (pintype "passive"))
    )
    (net (code "170") (name "unconnected-(JM1-Pad56)") (class "Default")
      (node (ref "JM1") (pin "56") (pinfunction "56_56") (pintype "passive"))
    )
    (net (code "171") (name "unconnected-(JM1-Pad58)") (class "Default")
      (node (ref "JM1") (pin "58") (pinfunction "58_58") (pintype "passive"))
    )
    (net (code "172") (name "unconnected-(JM1-Pad66)") (class "Default")
      (node (ref "JM1") (pin "66") (pinfunction "66_66") (pintype "passive"))
    )
    (net (code "173") (name "unconnected-(JM1-Pad68)") (class "Default")
      (node (ref "JM1") (pin "68") (pinfunction "68_68") (pintype "passive"))
    )
    (net (code "174") (name "unconnected-(JM1-Pad70)") (class "Default")
      (node (ref "JM1") (pin "70") (pinfunction "70_70") (pintype "passive"))
    )
    (net (code "175") (name "unconnected-(JM1-Pad72)") (class "Default")
      (node (ref "JM1") (pin "72") (pinfunction "72_72") (pintype "passive"))
    )
    (net (code "176") (name "unconnected-(JM1-Pad75)") (class "Default")
      (node (ref "JM1") (pin "75") (pinfunction "75_75") (pintype "passive"))
    )
    (net (code "177") (name "unconnected-(JM1-Pad77)") (class "Default")
      (node (ref "JM1") (pin "77") (pinfunction "77_77") (pintype "passive"))
    )
    (net (code "178") (name "unconnected-(JM1-Pad80)") (class "Default")
      (node (ref "JM1") (pin "80") (pinfunction "80_80") (pintype "passive"))
    )
    (net (code "179") (name "unconnected-(JM1-Pad82)") (class "Default")
      (node (ref "JM1") (pin "82") (pinfunction "82_82") (pintype "passive"))
    )
    (net (code "180") (name "unconnected-(JM1-Pad84)") (class "Default")
      (node (ref "JM1") (pin "84") (pinfunction "84_84") (pintype "passive"))
    )
    (net (code "181") (name "unconnected-(JM1-Pad86)") (class "Default")
      (node (ref "JM1") (pin "86") (pinfunction "86_86") (pintype "passive"))
    )
    (net (code "182") (name "unconnected-(JM1-Pad88)") (class "Default")
      (node (ref "JM1") (pin "88") (pinfunction "88_88") (pintype "passive"))
    )
    (net (code "183") (name "unconnected-(JM1-Pad91)") (class "Default")
      (node (ref "JM1") (pin "91") (pinfunction "91_91") (pintype "passive"))
    )
    (net (code "184") (name "unconnected-(JM1-Pad92)") (class "Default")
      (node (ref "JM1") (pin "92") (pinfunction "92_92") (pintype "passive"))
    )
    (net (code "185") (name "unconnected-(JM1-Pad98)") (class "Default")
      (node (ref "JM1") (pin "98") (pinfunction "98_98") (pintype "passive"))
    )
    (net (code "186") (name "unconnected-(JM1-Pad100)") (class "Default")
      (node (ref "JM1") (pin "100") (pinfunction "100_100") (pintype "passive"))
    )
    (net (code "187") (name "unconnected-(JM2-Pad6)") (class "Default")
      (node (ref "JM2") (pin "6") (pinfunction "6_6") (pintype "passive+no_connect"))
    )
    (net (code "188") (name "unconnected-(JM2-Pad9)") (class "Default")
      (node (ref "JM2") (pin "9") (pinfunction "9_9") (pintype "passive"))
    )
    (net (code "189") (name "unconnected-(JM2-Pad11)") (class "Default")
      (node (ref "JM2") (pin "11") (pinfunction "11_11") (pintype "passive"))
    )
    (net (code "190") (name "unconnected-(JM2-Pad12)") (class "Default")
      (node (ref "JM2") (pin "12") (pinfunction "12_12") (pintype "passive"))
    )
    (net (code "191") (name "unconnected-(JM2-Pad13)") (class "Default")
      (node (ref "JM2") (pin "13") (pinfunction "13_13") (pintype "passive"))
    )
    (net (code "192") (name "unconnected-(JM2-Pad14)") (class "Default")
      (node (ref "JM2") (pin "14") (pinfunction "14_14") (pintype "passive"))
    )
    (net (code "193") (name "unconnected-(JM2-Pad15)") (class "Default")
      (node (ref "JM2") (pin "15") (pinfunction "15_15") (pintype "passive"))
    )
    (net (code "194") (name "unconnected-(JM2-Pad16)") (class "Default")
      (node (ref "JM2") (pin "16") (pinfunction "16_16") (pintype "passive"))
    )
    (net (code "195") (name "unconnected-(JM2-Pad18)") (class "Default")
      (node (ref "JM2") (pin "18") (pinfunction "18_18") (pintype "passive"))
    )
    (net (code "196") (name "unconnected-(JM2-Pad20)") (class "Default")
      (node (ref "JM2") (pin "20") (pinfunction "20_20") (pintype "passive"))
    )
    (net (code "197") (name "unconnected-(JM2-Pad21)") (class "Default")
      (node (ref "JM2") (pin "21") (pinfunction "21_21") (pintype "passive"))
    )
    (net (code "198") (name "unconnected-(JM2-Pad22)") (class "Default")
      (node (ref "JM2") (pin "22") (pinfunction "22_22") (pintype "passive"))
    )
    (net (code "199") (name "unconnected-(JM2-Pad23)") (class "Default")
      (node (ref "JM2") (pin "23") (pinfunction "23_23") (pintype "passive"))
    )
    (net (code "200") (name "unconnected-(JM2-Pad24)") (class "Default")
      (node (ref "JM2") (pin "24") (pinfunction "24_24") (pintype "passive"))
    )
    (net (code "201") (name "unconnected-(JM2-Pad25)") (class "Default")
      (node (ref "JM2") (pin "25") (pinfunction "25_25") (pintype "passive"))
    )
    (net (code "202") (name "unconnected-(JM2-Pad26)") (class "Default")
      (node (ref "JM2") (pin "26") (pinfunction "26_26") (pintype "passive"))
    )
    (net (code "203") (name "unconnected-(JM2-Pad27)") (class "Default")
      (node (ref "JM2") (pin "27") (pinfunction "27_27") (pintype "passive"))
    )
    (net (code "204") (name "unconnected-(JM2-Pad28)") (class "Default")
      (node (ref "JM2") (pin "28") (pinfunction "28_28") (pintype "passive"))
    )
    (net (code "205") (name "unconnected-(JM2-Pad30)") (class "Default")
      (node (ref "JM2") (pin "30") (pinfunction "30_30") (pintype "passive+no_connect"))
    )
    (net (code "206") (name "unconnected-(JM2-Pad32)") (class "Default")
      (node (ref "JM2") (pin "32") (pinfunction "32_32") (pintype "passive"))
    )
    (net (code "207") (name "unconnected-(JM2-Pad34)") (class "Default")
      (node (ref "JM2") (pin "34") (pinfunction "34_34") (pintype "passive"))
    )
    (net (code "208") (name "unconnected-(JM2-Pad36)") (class "Default")
      (node (ref "JM2") (pin "36") (pinfunction "36_36") (pintype "passive"))
    )
    (net (code "209") (name "unconnected-(JM2-Pad38)") (class "Default")
      (node (ref "JM2") (pin "38") (pinfunction "38_38") (pintype "passive"))
    )
    (net (code "210") (name "unconnected-(JM2-Pad67)") (class "Default")
      (node (ref "JM2") (pin "67") (pinfunction "67_67") (pintype "passive"))
    )
    (net (code "211") (name "unconnected-(JM2-Pad71)") (class "Default")
      (node (ref "JM2") (pin "71") (pinfunction "71_71") (pintype "passive"))
    )
    (net (code "212") (name "unconnected-(JM2-Pad72)") (class "Default")
      (node (ref "JM2") (pin "72") (pinfunction "72_72") (pintype "passive"))
    )
    (net (code "213") (name "unconnected-(JM2-Pad73)") (class "Default")
      (node (ref "JM2") (pin "73") (pinfunction "73_73") (pintype "passive"))
    )
    (net (code "214") (name "unconnected-(JM2-Pad74)") (class "Default")
      (node (ref "JM2") (pin "74") (pinfunction "74_74") (pintype "passive"))
    )
    (net (code "215") (name "unconnected-(JM2-Pad75)") (class "Default")
      (node (ref "JM2") (pin "75") (pinfunction "75_75") (pintype "passive"))
    )
    (net (code "216") (name "unconnected-(JM2-Pad76)") (class "Default")
      (node (ref "JM2") (pin "76") (pinfunction "76_76") (pintype "passive"))
    )
    (net (code "217") (name "unconnected-(JM2-Pad77)") (class "Default")
      (node (ref "JM2") (pin "77") (pinfunction "77_77") (pintype "passive"))
    )
    (net (code "218") (name "unconnected-(JM2-Pad78)") (class "Default")
      (node (ref "JM2") (pin "78") (pinfunction "78_78") (pintype "passive"))
    )
    (net (code "219") (name "unconnected-(JM2-Pad81)") (class "Default")
      (node (ref "JM2") (pin "81") (pinfunction "81_81") (pintype "passive"))
    )
    (net (code "220") (name "unconnected-(JM2-Pad82)") (class "Default")
      (node (ref "JM2") (pin "82") (pinfunction "82_82") (pintype "passive"))
    )
    (net (code "221") (name "unconnected-(JM2-Pad83)") (class "Default")
      (node (ref "JM2") (pin "83") (pinfunction "83_83") (pintype "passive"))
    )
    (net (code "222") (name "unconnected-(JM2-Pad84)") (class "Default")
      (node (ref "JM2") (pin "84") (pinfunction "84_84") (pintype "passive"))
    )
    (net (code "223") (name "unconnected-(JM2-Pad85)") (class "Default")
      (node (ref "JM2") (pin "85") (pinfunction "85_85") (pintype "passive"))
    )
    (net (code "224") (name "unconnected-(JM2-Pad86)") (class "Default")
      (node (ref "JM2") (pin "86") (pinfunction "86_86") (pintype "passive"))
    )
    (net (code "225") (name "unconnected-(JM2-Pad87)") (class "Default")
      (node (ref "JM2") (pin "87") (pinfunction "87_87") (pintype "passive"))
    )
    (net (code "226") (name "unconnected-(JM2-Pad88)") (class "Default")
      (node (ref "JM2") (pin "88") (pinfunction "88_88") (pintype "passive"))
    )
    (net (code "227") (name "unconnected-(JM2-Pad90)") (class "Default")
      (node (ref "JM2") (pin "90") (pinfunction "90_90") (pintype "passive"))
    )
    (net (code "228") (name "unconnected-(JM2-Pad91)") (class "Default")
      (node (ref "JM2") (pin "91") (pinfunction "91_91") (pintype "passive"))
    )
    (net (code "229") (name "unconnected-(JM2-Pad93)") (class "Default")
      (node (ref "JM2") (pin "93") (pinfunction "93_93") (pintype "passive"))
    )
    (net (code "230") (name "unconnected-(JM2-Pad95)") (class "Default")
      (node (ref "JM2") (pin "95") (pinfunction "95_95") (pintype "passive"))
    )
    (net (code "231") (name "unconnected-(JM2-Pad97)") (class "Default")
      (node (ref "JM2") (pin "97") (pinfunction "97_97") (pintype "passive"))
    )
    (net (code "232") (name "unconnected-(JM2-Pad99)") (class "Default")
      (node (ref "JM2") (pin "99") (pinfunction "99_99") (pintype "passive"))
    )
    (net (code "233") (name "unconnected-(JM3-Pad1)") (class "Default")
      (node (ref "JM3") (pin "1") (pinfunction "1_1") (pintype "passive"))
    )
    (net (code "234") (name "unconnected-(JM3-Pad2)") (class "Default")
      (node (ref "JM3") (pin "2") (pinfunction "2_2") (pintype "passive"))
    )
    (net (code "235") (name "unconnected-(JM3-Pad3)") (class "Default")
      (node (ref "JM3") (pin "3") (pinfunction "3_3") (pintype "passive"))
    )
    (net (code "236") (name "unconnected-(JM3-Pad4)") (class "Default")
      (node (ref "JM3") (pin "4") (pinfunction "4_4") (pintype "passive"))
    )
    (net (code "237") (name "unconnected-(JM3-Pad31)") (class "Default")
      (node (ref "JM3") (pin "31") (pinfunction "31_31") (pintype "passive"))
    )
    (net (code "238") (name "unconnected-(JM3-Pad33)") (class "Default")
      (node (ref "JM3") (pin "33") (pinfunction "33_33") (pintype "passive"))
    )
    (net (code "239") (name "unconnected-(JM3-Pad37)") (class "Default")
      (node (ref "JM3") (pin "37") (pinfunction "37_37") (pintype "passive"))
    )
    (net (code "240") (name "unconnected-(JM3-Pad38)") (class "Default")
      (node (ref "JM3") (pin "38") (pinfunction "38_38") (pintype "passive"))
    )
    (net (code "241") (name "unconnected-(JM3-Pad39)") (class "Default")
      (node (ref "JM3") (pin "39") (pinfunction "39_39") (pintype "passive"))
    )
    (net (code "242") (name "unconnected-(JM3-Pad40)") (class "Default")
      (node (ref "JM3") (pin "40") (pinfunction "40_40") (pintype "passive"))
    )
    (net (code "243") (name "unconnected-(JM3-Pad41)") (class "Default")
      (node (ref "JM3") (pin "41") (pinfunction "41_41") (pintype "passive"))
    )
    (net (code "244") (name "unconnected-(JM3-Pad42)") (class "Default")
      (node (ref "JM3") (pin "42") (pinfunction "42_42") (pintype "passive"))
    )
    (net (code "245") (name "unconnected-(JM3-Pad43)") (class "Default")
      (node (ref "JM3") (pin "43") (pinfunction "43_43") (pintype "passive"))
    )
    (net (code "246") (name "unconnected-(JM3-Pad44)") (class "Default")
      (node (ref "JM3") (pin "44") (pinfunction "44_44") (pintype "passive"))
    )
    (net (code "247") (name "unconnected-(JM3-Pad47)") (class "Default")
      (node (ref "JM3") (pin "47") (pinfunction "47_47") (pintype "passive"))
    )
    (net (code "248") (name "unconnected-(JM3-Pad48)") (class "Default")
      (node (ref "JM3") (pin "48") (pinfunction "48_48") (pintype "passive"))
    )
    (net (code "249") (name "unconnected-(JM3-Pad49)") (class "Default")
      (node (ref "JM3") (pin "49") (pinfunction "49_49") (pintype "passive"))
    )
    (net (code "250") (name "unconnected-(JM3-Pad50)") (class "Default")
      (node (ref "JM3") (pin "50") (pinfunction "50_50") (pintype "passive"))
    )
    (net (code "251") (name "unconnected-(JM3-Pad51)") (class "Default")
      (node (ref "JM3") (pin "51") (pinfunction "51_51") (pintype "passive"))
    )
    (net (code "252") (name "unconnected-(JM3-Pad52)") (class "Default")
      (node (ref "JM3") (pin "52") (pinfunction "52_52") (pintype "passive"))
    )
    (net (code "253") (name "unconnected-(JM3-Pad53)") (class "Default")
      (node (ref "JM3") (pin "53") (pinfunction "53_53") (pintype "passive"))
    )
    (net (code "254") (name "unconnected-(JM3-Pad54)") (class "Default")
      (node (ref "JM3") (pin "54") (pinfunction "54_54") (pintype "passive"))
    )
    (net (code "255") (name "unconnected-(JM3-Pad55)") (class "Default")
      (node (ref "JM3") (pin "55") (pinfunction "55_55") (pintype "passive"))
    )
    (net (code "256") (name "unconnected-(JM3-Pad56)") (class "Default")
      (node (ref "JM3") (pin "56") (pinfunction "56_56") (pintype "passive"))
    )
    (net (code "257") (name "unconnected-(JM3-Pad57)") (class "Default")
      (node (ref "JM3") (pin "57") (pinfunction "57_57") (pintype "passive"))
    )
    (net (code "258") (name "unconnected-(JM3-Pad58)") (class "Default")
      (node (ref "JM3") (pin "58") (pinfunction "58_58") (pintype "passive"))
    )
    (net (code "259") (name "unconnected-(JM3-Pad59)") (class "Default")
      (node (ref "JM3") (pin "59") (pinfunction "59_59") (pintype "passive"))
    )
    (net (code "260") (name "unconnected-(U16-NC-Pad4)") (class "Default")
      (node (ref "U16") (pin "4") (pinfunction "NC_4") (pintype "passive+no_connect"))
    )
  )
)
